# untitled.net
KiCad netlist of a schematic drawn in EAGLE
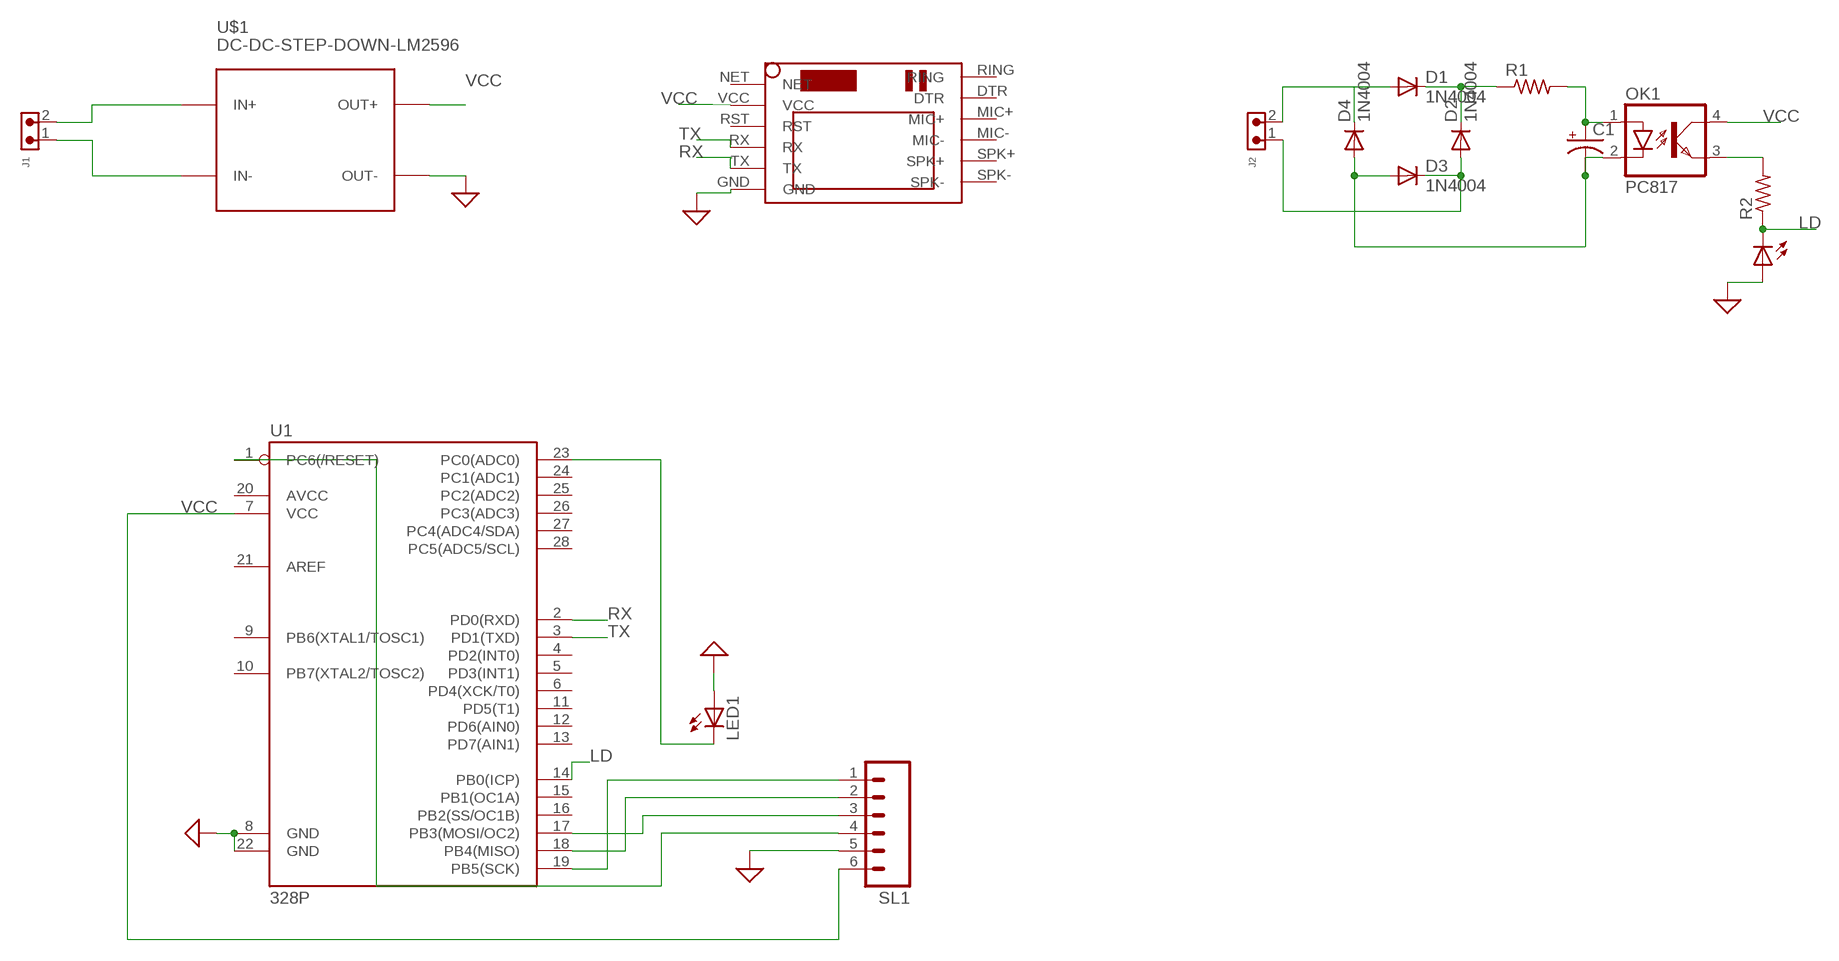
[diagram p0: schematic, sheet 1]

(export (version "E")
  (design (tool "Eeschema 10.0.6"))
  (components
    (comp (ref "C1")
      (value "CPOL-USE2.5-5")
      (footprint "eagle-import:E2,5-5")
      (libsource (lib "eagle-import") (part "CPOL-USE2.5-5"))
    )
    (comp (ref "D1")
      (value "1N4004")
      (footprint "eagle-import:DO41-10")
      (libsource (lib "eagle-import") (part "1N4004"))
    )
    (comp (ref "D2")
      (value "1N4004")
      (footprint "eagle-import:DO41-10")
      (libsource (lib "eagle-import") (part "1N4004"))
    )
    (comp (ref "D3")
      (value "1N4004")
      (footprint "eagle-import:DO41-10")
      (libsource (lib "eagle-import") (part "1N4004"))
    )
    (comp (ref "D4")
      (value "1N4004")
      (footprint "eagle-import:DO41-10")
      (libsource (lib "eagle-import") (part "1N4004"))
    )
    (comp (ref "J1")
      (value "691305530002")
      (footprint "eagle-import:691305530002")
      (libsource (lib "eagle-import") (part "691305530002"))
    )
    (comp (ref "J2")
      (value "691305530002")
      (footprint "eagle-import:691305530002")
      (libsource (lib "eagle-import") (part "691305530002"))
    )
    (comp (ref "LED1")
      (value "LED5MM")
      (footprint "eagle-import:LED5MM")
      (libsource (lib "eagle-import") (part "LED5MM"))
    )
    (comp (ref "LED2")
      (value "LED5MM")
      (footprint "eagle-import:LED5MM")
      (libsource (lib "eagle-import") (part "LED5MM"))
    )
    (comp (ref "OK1")
      (value "PC817")
      (footprint "eagle-import:DIL04")
      (fields (field (name "MPN") "PC817X4J000F"))
      (libsource (lib "eagle-import") (part "PC817"))
    )
    (comp (ref "R1")
      (value "R-US_0207/10")
      (footprint "eagle-import:0207_10")
      (libsource (lib "eagle-import") (part "R-US_0207/10"))
    )
    (comp (ref "R2")
      (value "R-US_0207/10")
      (footprint "eagle-import:0207_10")
      (libsource (lib "eagle-import") (part "R-US_0207/10"))
    )
    (comp (ref "SL1")
      (value "M06")
      (footprint "eagle-import:06P")
      (libsource (lib "eagle-import") (part "M06"))
    )
    (comp (ref "U$1")
      (value "DC-DC-STEP-DOWN-LM2596")
      (footprint "eagle-import:DC-DC-STEP-DOWN-LM2596")
      (libsource (lib "eagle-import") (part "DC-DC-STEP-DOWN-LM2596"))
    )
    (comp (ref "U$2")
      (value "SIM800LMODULE")
      (footprint "eagle-import:SIM800LMODULE")
      (libsource (lib "eagle-import") (part "SIM800LMODULE"))
    )
    (comp (ref "U1")
      (value "328P")
      (footprint "eagle-import:DIP28")
      (libsource (lib "eagle-import") (part "ATMEGA328P_PDIP"))
    )
  )
  (nets
    (net (code "1") (name "/LD") (class "Default")
      (node (ref "LED2") (pin "K") (pinfunction "C_K") (pintype "passive"))
      (node (ref "OK1") (pin "3") (pinfunction "EMIT_3") (pintype "passive"))
      (node (ref "R2") (pin "1") (pinfunction "1_1") (pintype "passive"))
      (node (ref "R2") (pin "2") (pinfunction "2_2") (pintype "passive"))
      (node (ref "U1") (pin "14") (pinfunction "PB0(ICP)_14") (pintype "bidirectional"))
    )
    (net (code "2") (name "/RX") (class "Default")
      (node (ref "U$2") (pin "TX") (pinfunction "TX_TX") (pintype "bidirectional"))
      (node (ref "U1") (pin "2") (pinfunction "PD0(RXD)_2") (pintype "bidirectional"))
    )
    (net (code "3") (name "/TX") (class "Default")
      (node (ref "U$2") (pin "RX") (pinfunction "RX_RX") (pintype "bidirectional"))
      (node (ref "U1") (pin "3") (pinfunction "PD1(TXD)_3") (pintype "bidirectional"))
    )
    (net (code "4") (name "/VCC") (class "Default")
      (node (ref "OK1") (pin "4") (pinfunction "COL_4") (pintype "passive"))
      (node (ref "SL1") (pin "6") (pinfunction "6_6") (pintype "passive"))
      (node (ref "U$1") (pin "OUT+") (pinfunction "OUT+_OUT+") (pintype "bidirectional"))
      (node (ref "U$2") (pin "VCC") (pinfunction "VCC_VCC") (pintype "bidirectional"))
      (node (ref "U1") (pin "7") (pinfunction "VCC_7") (pintype "bidirectional"))
    )
    (net (code "5") (name "Net-(D1-PadA)") (class "Default")
      (node (ref "D1") (pin "A") (pinfunction "A_A") (pintype "passive"))
      (node (ref "D4") (pin "C") (pinfunction "C_C") (pintype "passive"))
      (node (ref "J2") (pin "2") (pinfunction "2_2") (pintype "passive"))
    )
    (net (code "6") (name "Net-(D1-PadC)") (class "Default")
      (node (ref "D1") (pin "C") (pinfunction "C_C") (pintype "passive"))
      (node (ref "D2") (pin "C") (pinfunction "C_C") (pintype "passive"))
      (node (ref "R1") (pin "1") (pinfunction "1_1") (pintype "passive"))
    )
    (net (code "7") (name "Net-(D2-PadA)") (class "Default")
      (node (ref "D2") (pin "A") (pinfunction "A_A") (pintype "passive"))
      (node (ref "D3") (pin "C") (pinfunction "C_C") (pintype "passive"))
      (node (ref "J2") (pin "1") (pinfunction "1_1") (pintype "passive"))
    )
    (net (code "8") (name "Net-(J1-Pad1)") (class "Default")
      (node (ref "J1") (pin "1") (pinfunction "1_1") (pintype "passive"))
      (node (ref "U$1") (pin "IN-") (pinfunction "IN-_IN-") (pintype "bidirectional"))
    )
    (net (code "9") (name "Net-(J1-Pad2)") (class "Default")
      (node (ref "J1") (pin "2") (pinfunction "2_2") (pintype "passive"))
      (node (ref "U$1") (pin "IN+") (pinfunction "IN+_IN+") (pintype "bidirectional"))
    )
    (net (code "10") (name "Net-(LED1-C)") (class "Default")
      (node (ref "LED1") (pin "K") (pinfunction "C_K") (pintype "passive"))
      (node (ref "U1") (pin "23") (pinfunction "PC0(ADC0)_23") (pintype "bidirectional"))
    )
    (net (code "11") (name "Net-(OK1-A)") (class "Default")
      (node (ref "C1") (pin "+") (pinfunction "+_+") (pintype "passive"))
      (node (ref "OK1") (pin "1") (pinfunction "A_1") (pintype "passive"))
      (node (ref "R1") (pin "2") (pinfunction "2_2") (pintype "passive"))
    )
    (net (code "12") (name "Net-(OK1-C)") (class "Default")
      (node (ref "C1") (pin "-") (pinfunction "-_-") (pintype "passive"))
      (node (ref "D3") (pin "A") (pinfunction "A_A") (pintype "passive"))
      (node (ref "D4") (pin "A") (pinfunction "A_A") (pintype "passive"))
      (node (ref "OK1") (pin "2") (pinfunction "C_2") (pintype "passive"))
    )
    (net (code "13") (name "Net-(U1-PB3(MOSI{slash}OC2))") (class "Default")
      (node (ref "SL1") (pin "3") (pinfunction "3_3") (pintype "passive"))
      (node (ref "U1") (pin "17") (pinfunction "PB3(MOSI/OC2)_17") (pintype "bidirectional"))
    )
    (net (code "14") (name "Net-(U1-PB4(MISO))") (class "Default")
      (node (ref "SL1") (pin "2") (pinfunction "2_2") (pintype "passive"))
      (node (ref "U1") (pin "18") (pinfunction "PB4(MISO)_18") (pintype "bidirectional"))
    )
    (net (code "15") (name "Net-(U1-PB5(SCK))") (class "Default")
      (node (ref "SL1") (pin "1") (pinfunction "1_1") (pintype "passive"))
      (node (ref "U1") (pin "19") (pinfunction "PB5(SCK)_19") (pintype "bidirectional"))
    )
    (net (code "16") (name "Net-(U1-PC6({slash}RESET))") (class "Default")
      (node (ref "SL1") (pin "4") (pinfunction "4_4") (pintype "passive"))
      (node (ref "U1") (pin "1") (pinfunction "PC6(/RESET)_1") (pintype "bidirectional"))
    )
    (net (code "17") (name "SUP") (class "Default")
      (node (ref "LED1") (pin "A") (pinfunction "A_A") (pintype "passive"))
      (node (ref "LED2") (pin "A") (pinfunction "A_A") (pintype "passive"))
      (node (ref "SL1") (pin "5") (pinfunction "5_5") (pintype "passive"))
      (node (ref "U$1") (pin "OUT-") (pinfunction "OUT-_OUT-") (pintype "bidirectional"))
      (node (ref "U$2") (pin "GND") (pinfunction "GND_GND") (pintype "bidirectional"))
      (node (ref "U1") (pin "22") (pinfunction "GND_22") (pintype "bidirectional"))
      (node (ref "U1") (pin "8") (pinfunction "GND_8") (pintype "bidirectional"))
    )
    (net (code "18") (name "unconnected-(U$2-PadDTR)") (class "Default")
      (node (ref "U$2") (pin "DTR") (pinfunction "DTR_DTR") (pintype "bidirectional"))
    )
    (net (code "19") (name "unconnected-(U$2-PadMIC+)") (class "Default")
      (node (ref "U$2") (pin "MIC+") (pinfunction "MIC+_MIC+") (pintype "bidirectional"))
    )
    (net (code "20") (name "unconnected-(U$2-PadMIC-)") (class "Default")
      (node (ref "U$2") (pin "MIC-") (pinfunction "MIC-_MIC-") (pintype "bidirectional"))
    )
    (net (code "21") (name "unconnected-(U$2-PadNET)") (class "Default")
      (node (ref "U$2") (pin "NET") (pinfunction "NET_NET") (pintype "bidirectional"))
    )
    (net (code "22") (name "unconnected-(U$2-PadRING)") (class "Default")
      (node (ref "U$2") (pin "RING") (pinfunction "RING_RING") (pintype "bidirectional"))
    )
    (net (code "23") (name "unconnected-(U$2-PadRST)") (class "Default")
      (node (ref "U$2") (pin "RST") (pinfunction "RST_RST") (pintype "bidirectional"))
    )
    (net (code "24") (name "unconnected-(U$2-PadSPK+)") (class "Default")
      (node (ref "U$2") (pin "SPK+") (pinfunction "SPK+_SPK+") (pintype "bidirectional"))
    )
    (net (code "25") (name "unconnected-(U$2-PadSPK-)") (class "Default")
      (node (ref "U$2") (pin "SPK-") (pinfunction "SPK-_SPK-") (pintype "bidirectional"))
    )
    (net (code "26") (name "unconnected-(U1-AREF-Pad21)") (class "Default")
      (node (ref "U1") (pin "21") (pinfunction "AREF_21") (pintype "bidirectional"))
    )
    (net (code "27") (name "unconnected-(U1-AVCC-Pad20)") (class "Default")
      (node (ref "U1") (pin "20") (pinfunction "AVCC_20") (pintype "bidirectional"))
    )
    (net (code "28") (name "unconnected-(U1-PB1(OC1A)-Pad15)") (class "Default")
      (node (ref "U1") (pin "15") (pinfunction "PB1(OC1A)_15") (pintype "bidirectional"))
    )
    (net (code "29") (name "unconnected-(U1-PB2(SS{slash}OC1B)-Pad16)") (class "Default")
      (node (ref "U1") (pin "16") (pinfunction "PB2(SS/OC1B)_16") (pintype "bidirectional"))
    )
    (net (code "30") (name "unconnected-(U1-PB6(XTAL1{slash}TOSC1)-Pad9)") (class "Default")
      (node (ref "U1") (pin "9") (pinfunction "PB6(XTAL1/TOSC1)_9") (pintype "bidirectional"))
    )
    (net (code "31") (name "unconnected-(U1-PB7(XTAL2{slash}TOSC2)-Pad10)") (class "Default")
      (node (ref "U1") (pin "10") (pinfunction "PB7(XTAL2/TOSC2)_10") (pintype "bidirectional"))
    )
    (net (code "32") (name "unconnected-(U1-PC1(ADC1)-Pad24)") (class "Default")
      (node (ref "U1") (pin "24") (pinfunction "PC1(ADC1)_24") (pintype "bidirectional"))
    )
    (net (code "33") (name "unconnected-(U1-PC2(ADC2)-Pad25)") (class "Default")
      (node (ref "U1") (pin "25") (pinfunction "PC2(ADC2)_25") (pintype "bidirectional"))
    )
    (net (code "34") (name "unconnected-(U1-PC3(ADC3)-Pad26)") (class "Default")
      (node (ref "U1") (pin "26") (pinfunction "PC3(ADC3)_26") (pintype "bidirectional"))
    )
    (net (code "35") (name "unconnected-(U1-PC4(ADC4{slash}SDA)-Pad27)") (class "Default")
      (node (ref "U1") (pin "27") (pinfunction "PC4(ADC4/SDA)_27") (pintype "bidirectional"))
    )
    (net (code "36") (name "unconnected-(U1-PC5(ADC5{slash}SCL)-Pad28)") (class "Default")
      (node (ref "U1") (pin "28") (pinfunction "PC5(ADC5/SCL)_28") (pintype "bidirectional"))
    )
    (net (code "37") (name "unconnected-(U1-PD2(INT0)-Pad4)") (class "Default")
      (node (ref "U1") (pin "4") (pinfunction "PD2(INT0)_4") (pintype "bidirectional"))
    )
    (net (code "38") (name "unconnected-(U1-PD3(INT1)-Pad5)") (class "Default")
      (node (ref "U1") (pin "5") (pinfunction "PD3(INT1)_5") (pintype "bidirectional"))
    )
    (net (code "39") (name "unconnected-(U1-PD4(XCK{slash}T0)-Pad6)") (class "Default")
      (node (ref "U1") (pin "6") (pinfunction "PD4(XCK/T0)_6") (pintype "bidirectional"))
    )
    (net (code "40") (name "unconnected-(U1-PD5(T1)-Pad11)") (class "Default")
      (node (ref "U1") (pin "11") (pinfunction "PD5(T1)_11") (pintype "bidirectional"))
    )
    (net (code "41") (name "unconnected-(U1-PD6(AIN0)-Pad12)") (class "Default")
      (node (ref "U1") (pin "12") (pinfunction "PD6(AIN0)_12") (pintype "bidirectional"))
    )
    (net (code "42") (name "unconnected-(U1-PD7(AIN1)-Pad13)") (class "Default")
      (node (ref "U1") (pin "13") (pinfunction "PD7(AIN1)_13") (pintype "bidirectional"))
    )
  )
)
